# 10_-_SATA_CSI.net
KiCad netlist of a schematic drawn in Altium Designer
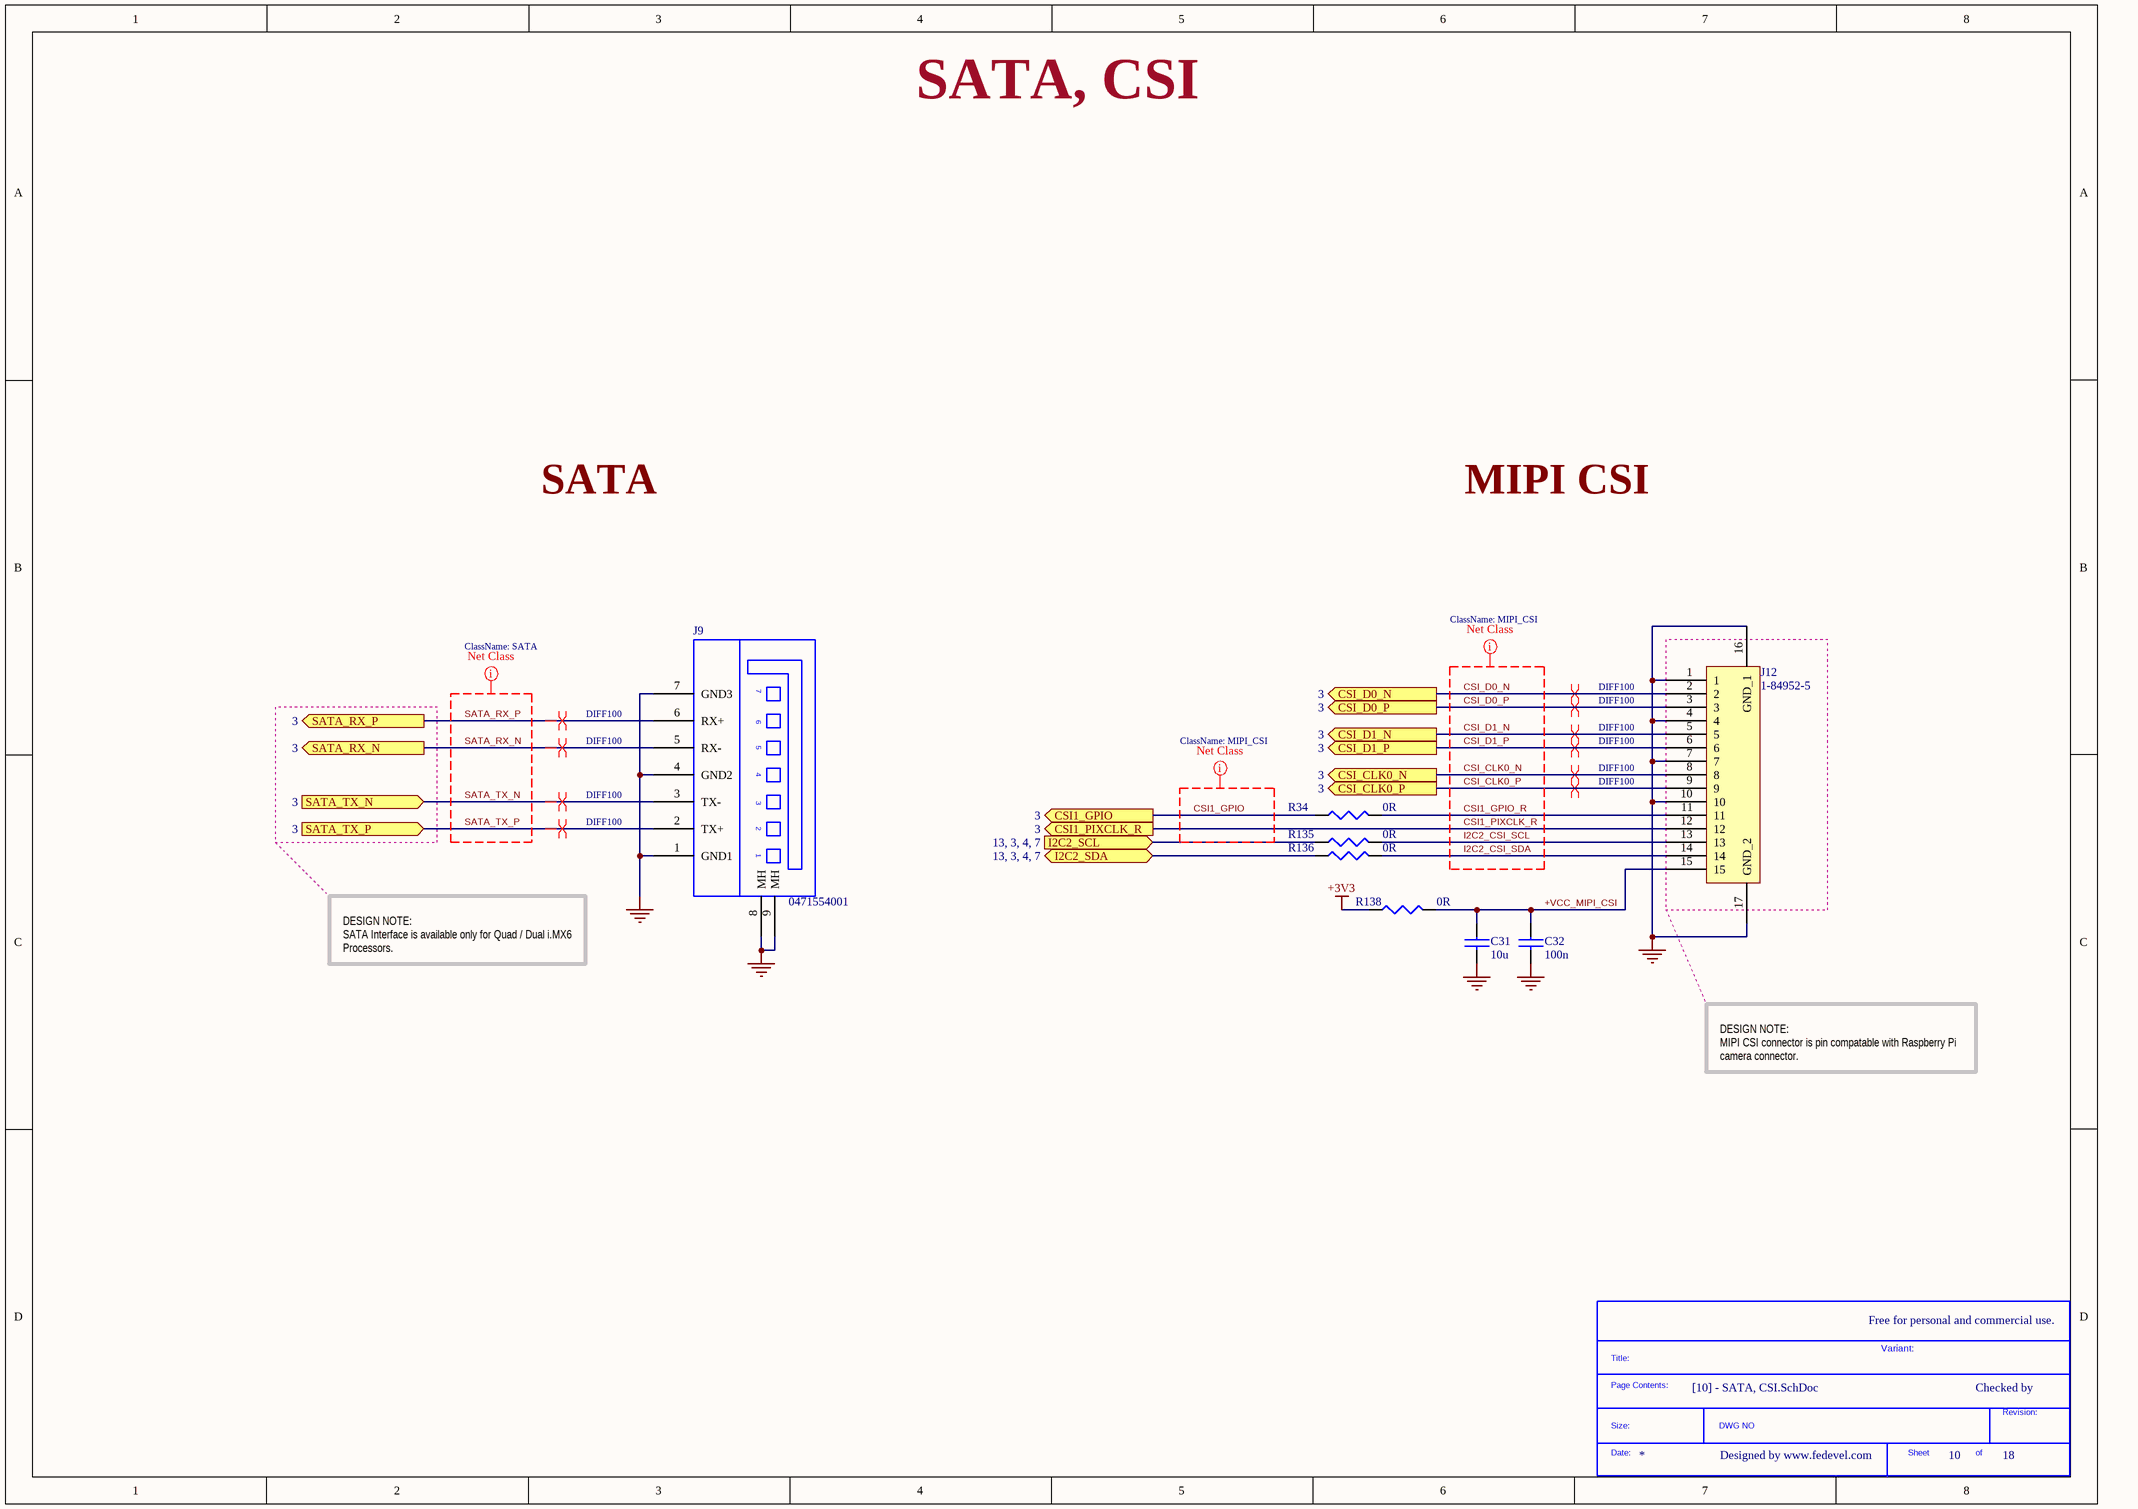
[diagram p0: [10] - SATA, CSI.SchDoc]

(export (version "E")
  (design (tool "Eeschema 10.0.6"))
  (components
    (comp (ref "*") (value "SDTitleBlock") (libsource (lib "*") (part "SDTitleBlock")))
    (comp (ref "C31")
      (value "10u")
      (footprint "C0603")
      (description "CAP CER 10UF 6.3V X5R 20% 0603")
      (fields
        (field (name "MANUFACTURER") "TDK Corporation")
        (field (name "MANUFACTURER PART NUMBER") "C1608X5R0J106M")
      )
      (libsource (lib "Integrated_Library_FEDEVEL_APR_2015") (part "C1608X5R0J106M"))
    )
    (comp (ref "C32")
      (value "100n")
      (footprint "C0402")
      (description "CAP CER .10UF 50V X5R 10% 0402")
      (fields
        (field (name "MANUFACTURER") "TDK Corporation")
        (field (name "MANUFACTURER PART NUMBER") "C1005X5R1H104K")
      )
      (libsource (lib "Integrated_Library_FEDEVEL_APR_2015") (part "C1005X5R1H104K"))
    )
    (comp (ref "J9")
      (value "0471554001")
      (footprint "SATA_VERTICAL")
      (description "CONN SATA HDR 7POS PCB VERT")
      (fields (field (name "MANUFACTURER") "Molex Inc"))
      (libsource (lib "Integrated_Library_FEDEVEL_APR_2015") (part "0471554001"))
    )
    (comp (ref "J12")
      (value "1-84952-5")
      (footprint "ZIF_RA_BOTTOM_15x1mm")
      (description "CONN FPC BOTTOM 15POS 1.00MM R/A")
      (fields
        (field (name "MANUFACTURER") "TE Connectivity")
        (field (name ".CREATOR") "MM")
        (field (name ".CHECKED PCB") "MM")
        (field (name ".CHECKED SCH") "MM")
      )
      (libsource (lib "Integrated_Library_FEDEVEL_APR_2015") (part "1-84952-5"))
    )
    (comp (ref "R34")
      (value "0R")
      (footprint "R0402")
      (description "RES 0.0 OHM 1/16W 0402 SMD")
      (fields
        (field (name "MANUFACTURER") "Yageo")
        (field (name "MANUFACTURER PART NUMBER") "RC0402JR-070RL")
      )
      (libsource (lib "Integrated_Library_FEDEVEL_APR_2015") (part "RC0402JR-070RL"))
    )
    (comp (ref "R135")
      (value "0R")
      (footprint "R0402")
      (description "RES 0.0 OHM 1/16W 0402 SMD")
      (fields
        (field (name "MANUFACTURER") "Yageo")
        (field (name "MANUFACTURER PART NUMBER") "RC0402JR-070RL")
      )
      (libsource (lib "Integrated_Library_FEDEVEL_APR_2015") (part "RC0402JR-070RL"))
    )
    (comp (ref "R136")
      (value "0R")
      (footprint "R0402")
      (description "RES 0.0 OHM 1/16W 0402 SMD")
      (fields
        (field (name "MANUFACTURER") "Yageo")
        (field (name "MANUFACTURER PART NUMBER") "RC0402JR-070RL")
      )
      (libsource (lib "Integrated_Library_FEDEVEL_APR_2015") (part "RC0402JR-070RL"))
    )
    (comp (ref "R138")
      (value "0R")
      (footprint "R0402")
      (description "RES 0.0 OHM 1/16W 0402 SMD")
      (fields
        (field (name "MANUFACTURER") "Yageo")
        (field (name "MANUFACTURER PART NUMBER") "RC0402JR-070RL")
      )
      (libsource (lib "Integrated_Library_FEDEVEL_APR_2015") (part "RC0402JR-070RL"))
    )
  )
  (nets
    (net (code "1") (name "+3V3") (class "Default")
      (node (ref "R138") (pin "1") (pinfunction "1_1") (pintype "passive"))
    )
    (net (code "2") (name "/+VCC_MIPI_CSI") (class "Default")
      (node (ref "C31") (pin "1") (pinfunction "1_1") (pintype "passive"))
      (node (ref "C32") (pin "1") (pinfunction "1_1") (pintype "passive"))
      (node (ref "J12") (pin "15") (pinfunction "15_15") (pintype "passive"))
      (node (ref "R138") (pin "2") (pinfunction "2_2") (pintype "passive"))
    )
    (net (code "3") (name "/CSI1_GPIO") (class "Default")
      (node (ref "R34") (pin "2") (pinfunction "2_2") (pintype "passive"))
    )
    (net (code "4") (name "/CSI1_GPIO_R") (class "Default")
      (node (ref "J12") (pin "11") (pinfunction "11_11") (pintype "passive"))
      (node (ref "R34") (pin "1") (pinfunction "1_1") (pintype "passive"))
    )
    (net (code "5") (name "/CSI1_PIXCLK_R") (class "Default")
      (node (ref "J12") (pin "12") (pinfunction "12_12") (pintype "passive"))
    )
    (net (code "6") (name "/CSI_CLK0_N") (class "Default")
      (node (ref "J12") (pin "8") (pinfunction "8_8") (pintype "passive"))
    )
    (net (code "7") (name "/CSI_CLK0_P") (class "Default")
      (node (ref "J12") (pin "9") (pinfunction "9_9") (pintype "passive"))
    )
    (net (code "8") (name "/CSI_D0_N") (class "Default")
      (node (ref "J12") (pin "2") (pinfunction "2_2") (pintype "passive"))
    )
    (net (code "9") (name "/CSI_D0_P") (class "Default")
      (node (ref "J12") (pin "3") (pinfunction "3_3") (pintype "passive"))
    )
    (net (code "10") (name "/CSI_D1_N") (class "Default")
      (node (ref "J12") (pin "5") (pinfunction "5_5") (pintype "passive"))
    )
    (net (code "11") (name "/CSI_D1_P") (class "Default")
      (node (ref "J12") (pin "6") (pinfunction "6_6") (pintype "passive"))
    )
    (net (code "12") (name "/I2C2_CSI_SCL") (class "Default")
      (node (ref "J12") (pin "13") (pinfunction "13_13") (pintype "passive"))
      (node (ref "R135") (pin "1") (pinfunction "1_1") (pintype "passive"))
    )
    (net (code "13") (name "/I2C2_CSI_SDA") (class "Default")
      (node (ref "J12") (pin "14") (pinfunction "14_14") (pintype "passive"))
      (node (ref "R136") (pin "1") (pinfunction "1_1") (pintype "passive"))
    )
    (net (code "14") (name "/I2C2_SCL") (class "Default")
      (node (ref "R135") (pin "2") (pinfunction "2_2") (pintype "passive"))
    )
    (net (code "15") (name "/I2C2_SDA") (class "Default")
      (node (ref "R136") (pin "2") (pinfunction "2_2") (pintype "passive"))
    )
    (net (code "16") (name "/SATA_RX_N") (class "Default")
      (node (ref "J9") (pin "5") (pinfunction "RX-_5") (pintype "passive"))
    )
    (net (code "17") (name "/SATA_RX_P") (class "Default")
      (node (ref "J9") (pin "6") (pinfunction "RX+_6") (pintype "passive"))
    )
    (net (code "18") (name "/SATA_TX_N") (class "Default")
      (node (ref "J9") (pin "3") (pinfunction "TX-_3") (pintype "passive"))
    )
    (net (code "19") (name "/SATA_TX_P") (class "Default")
      (node (ref "J9") (pin "2") (pinfunction "TX+_2") (pintype "passive"))
    )
    (net (code "20") (name "GND") (class "Default")
      (node (ref "C31") (pin "2") (pinfunction "2_2") (pintype "passive"))
      (node (ref "C32") (pin "2") (pinfunction "2_2") (pintype "passive"))
      (node (ref "J12") (pin "1") (pinfunction "1_1") (pintype "passive"))
      (node (ref "J12") (pin "10") (pinfunction "10_10") (pintype "passive"))
      (node (ref "J12") (pin "16") (pinfunction "GND_1_16") (pintype "passive"))
      (node (ref "J12") (pin "17") (pinfunction "GND_2_17") (pintype "passive"))
      (node (ref "J12") (pin "4") (pinfunction "4_4") (pintype "passive"))
      (node (ref "J12") (pin "7") (pinfunction "7_7") (pintype "passive"))
      (node (ref "J9") (pin "1") (pinfunction "GND1_1") (pintype "passive"))
      (node (ref "J9") (pin "4") (pinfunction "GND2_4") (pintype "passive"))
      (node (ref "J9") (pin "7") (pinfunction "GND3_7") (pintype "passive"))
      (node (ref "J9") (pin "8") (pinfunction "MH_8") (pintype "passive"))
      (node (ref "J9") (pin "9") (pinfunction "MH_9") (pintype "passive"))
    )
  )
)
